# fpc.net
KiCad netlist of a schematic drawn in Altium Designer
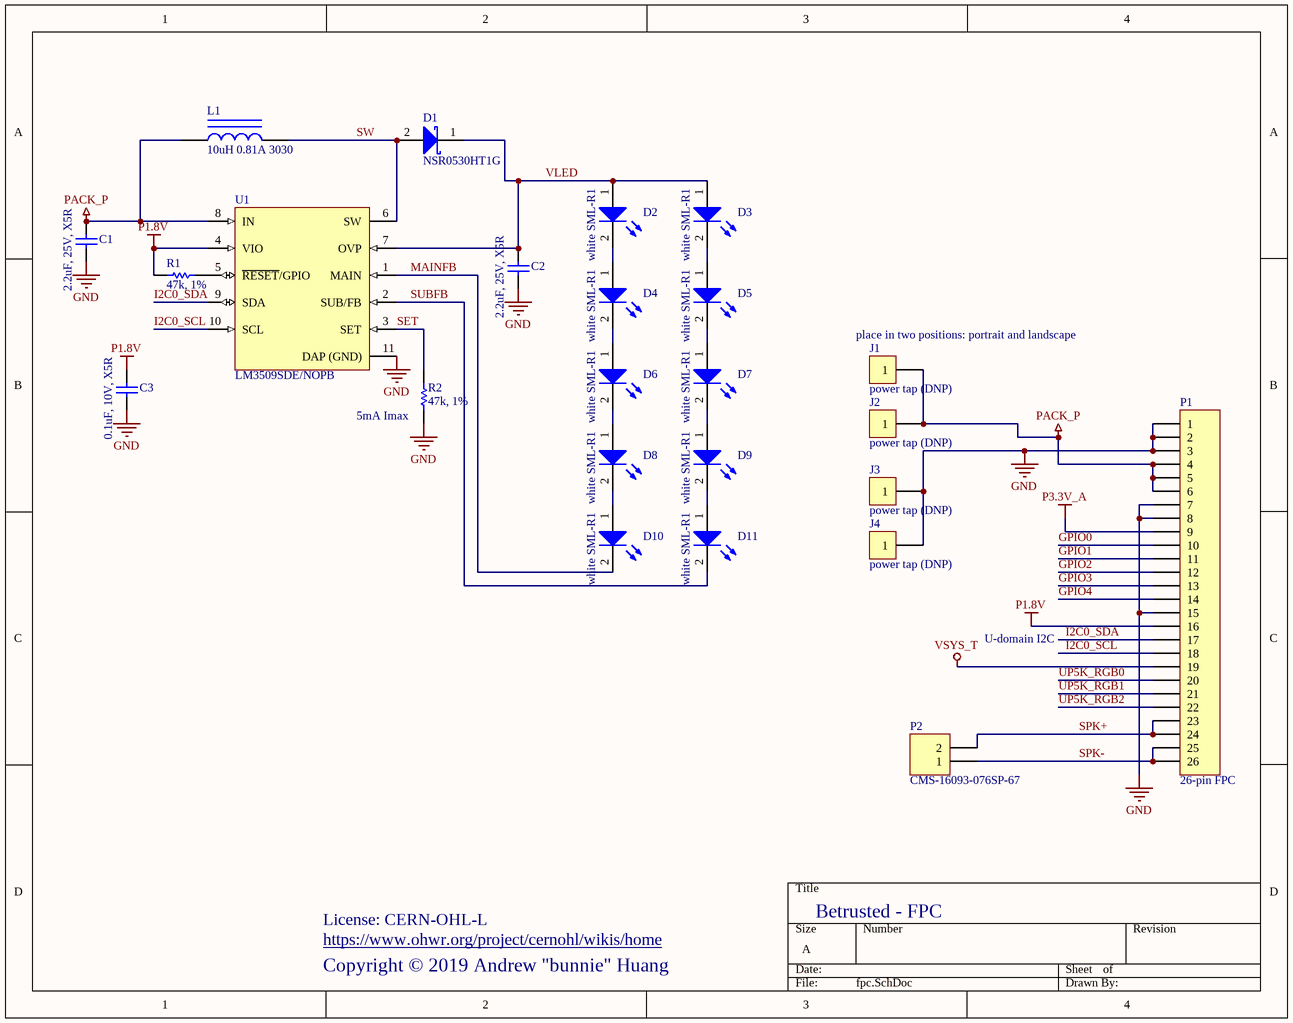
[diagram p0: fpc.SchDoc]

(export (version "E")
  (design (tool "Eeschema 10.0.6"))
  (components
    (comp (ref "C1")
      (value "2.2uF, 25V, X5R")
      (footprint "B_CAP0603")
      (description "Capacitor (Semiconductor SIM Model)")
      (fields (field (name "MPN") "GRM188R61E225MA12D"))
      (libsource (lib "Miscellaneous Devices") (part "Cap Semi"))
    )
    (comp (ref "C2")
      (value "2.2uF, 25V, X5R")
      (footprint "B_CAP0603")
      (description "Capacitor (Semiconductor SIM Model)")
      (fields (field (name "MPN") "GRM188R61E225MA12D"))
      (libsource (lib "Miscellaneous Devices") (part "Cap Semi"))
    )
    (comp (ref "C3")
      (value "0.1uF, 10V, X5R")
      (footprint "B_CAP0402")
      (description "Capacitor (Semiconductor SIM Model)")
      (fields (field (name "MPN") "CL05A104KP5NNNC"))
      (libsource (lib "Miscellaneous Devices") (part "Cap Semi"))
    )
    (comp (ref "D1")
      (value "NSR0530HT1G")
      (footprint "SOD-323")
      (description "Schottky Rectifier")
      (libsource (lib "Miscellaneous Devices") (part "Diode 11DQ03"))
    )
    (comp (ref "D2")
      (value "white SML-R1")
      (footprint "ROHM_SML-R1")
      (description "Red LED")
      (fields (field (name "MPN") "SMLR13WBDW") (field (name "PUBLISHER") "Altium Limited"))
      (libsource (lib "Miscellaneous Devices") (part "LED2"))
    )
    (comp (ref "D3")
      (value "white SML-R1")
      (footprint "ROHM_SML-R1")
      (description "Red LED")
      (fields (field (name "MPN") "SMLR13WBDW") (field (name "PUBLISHER") "Altium Limited"))
      (libsource (lib "Miscellaneous Devices") (part "LED2"))
    )
    (comp (ref "D4")
      (value "white SML-R1")
      (footprint "ROHM_SML-R1")
      (description "Red LED")
      (fields (field (name "MPN") "SMLR13WBDW") (field (name "PUBLISHER") "Altium Limited"))
      (libsource (lib "Miscellaneous Devices") (part "LED2"))
    )
    (comp (ref "D5")
      (value "white SML-R1")
      (footprint "ROHM_SML-R1")
      (description "Red LED")
      (fields (field (name "MPN") "SMLR13WBDW") (field (name "PUBLISHER") "Altium Limited"))
      (libsource (lib "Miscellaneous Devices") (part "LED2"))
    )
    (comp (ref "D6")
      (value "white SML-R1")
      (footprint "ROHM_SML-R1")
      (description "Red LED")
      (fields (field (name "MPN") "SMLR13WBDW") (field (name "PUBLISHER") "Altium Limited"))
      (libsource (lib "Miscellaneous Devices") (part "LED2"))
    )
    (comp (ref "D7")
      (value "white SML-R1")
      (footprint "ROHM_SML-R1")
      (description "Red LED")
      (fields (field (name "MPN") "SMLR13WBDW") (field (name "PUBLISHER") "Altium Limited"))
      (libsource (lib "Miscellaneous Devices") (part "LED2"))
    )
    (comp (ref "D8")
      (value "white SML-R1")
      (footprint "ROHM_SML-R1")
      (description "Red LED")
      (fields (field (name "MPN") "SMLR13WBDW") (field (name "PUBLISHER") "Altium Limited"))
      (libsource (lib "Miscellaneous Devices") (part "LED2"))
    )
    (comp (ref "D9")
      (value "white SML-R1")
      (footprint "ROHM_SML-R1")
      (description "Red LED")
      (fields (field (name "MPN") "SMLR13WBDW") (field (name "PUBLISHER") "Altium Limited"))
      (libsource (lib "Miscellaneous Devices") (part "LED2"))
    )
    (comp (ref "D10")
      (value "white SML-R1")
      (footprint "ROHM_SML-R1")
      (description "Red LED")
      (fields (field (name "MPN") "SMLR13WBDW") (field (name "PUBLISHER") "Altium Limited"))
      (libsource (lib "Miscellaneous Devices") (part "LED2"))
    )
    (comp (ref "D11")
      (value "white SML-R1")
      (footprint "ROHM_SML-R1")
      (description "Red LED")
      (fields (field (name "MPN") "SMLR13WBDW") (field (name "PUBLISHER") "Altium Limited"))
      (libsource (lib "Miscellaneous Devices") (part "LED2"))
    )
    (comp (ref "J1")
      (value "power tap (DNP)")
      (footprint "RESTAP-0603")
      (description "Connector")
      (fields (field (name "MPN") "DNP"))
      (libsource (lib "*") (part "CON1"))
    )
    (comp (ref "J2")
      (value "power tap (DNP)")
      (footprint "RESTAP-0603")
      (description "Connector")
      (fields (field (name "MPN") "DNP"))
      (libsource (lib "*") (part "CON1"))
    )
    (comp (ref "J3")
      (value "power tap (DNP)")
      (footprint "RESTAP-0603")
      (description "Connector")
      (fields (field (name "MPN") "DNP"))
      (libsource (lib "*") (part "CON1"))
    )
    (comp (ref "J4")
      (value "power tap (DNP)")
      (footprint "RESTAP-0603")
      (description "Connector")
      (fields (field (name "MPN") "DNP"))
      (libsource (lib "*") (part "CON1"))
    )
    (comp (ref "L1")
      (value "10uH 0.81A 3030")
      (footprint "B_IND3030_MUR")
      (description "Magnetic-Core Inductor")
      (fields (field (name "MPN") "LQH3NPN100MJRL"))
      (libsource (lib "Miscellaneous Devices") (part "Inductor Iron"))
    )
    (comp (ref "P1")
      (value "26-pin FPC")
      (footprint "HRS_FH34SRJ-26S-FPC")
      (description "26 Pin FPC footprint")
      (fields (field (name "MPN") "DNP"))
      (libsource (lib "commonsch-new") (part "FPC-26"))
    )
    (comp (ref "P2")
      (value "CMS-16093-076SP-67")
      (footprint "CUI_CMS-16093-076SP-67")
      (fields (field (name "PUBLISHER") "Altium Limited"))
      (libsource (lib "Miscellaneous Connectors") (part "Header 2"))
    )
    (comp (ref "R1")
      (value "47k, 1%")
      (footprint "B_RES0402")
      (description "Resistor")
      (fields (field (name "MPN") "ANY"))
      (libsource (lib "Miscellaneous Devices") (part "Res1"))
    )
    (comp (ref "R2")
      (value "47k, 1%")
      (footprint "B_RES0402")
      (description "Resistor")
      (fields (field (name "MPN") "ANY"))
      (libsource (lib "Miscellaneous Devices") (part "Res1"))
    )
    (comp (ref "U1")
      (value "LM3509SDE/NOPB")
      (footprint "DSC0010A_V")
      (libsource (lib "commonsch-new") (part "LM3509SDE/NOPB"))
    )
  )
  (nets
    (net (code "1") (name "/GPIO0") (class "Default")
      (node (ref "P1") (pin "10") (pinfunction "10_10") (pintype "passive"))
    )
    (net (code "2") (name "/GPIO1") (class "Default")
      (node (ref "P1") (pin "11") (pinfunction "11_11") (pintype "passive"))
    )
    (net (code "3") (name "/GPIO2") (class "Default")
      (node (ref "P1") (pin "12") (pinfunction "12_12") (pintype "passive"))
    )
    (net (code "4") (name "/GPIO3") (class "Default")
      (node (ref "P1") (pin "13") (pinfunction "13_13") (pintype "passive"))
    )
    (net (code "5") (name "/GPIO4") (class "Default")
      (node (ref "P1") (pin "14") (pinfunction "14_14") (pintype "passive"))
    )
    (net (code "6") (name "/I2C0_SCL") (class "Default")
      (node (ref "P1") (pin "18") (pinfunction "18_18") (pintype "passive"))
      (node (ref "U1") (pin "10") (pinfunction "SCL_10") (pintype "input"))
    )
    (net (code "7") (name "/I2C0_SDA") (class "Default")
      (node (ref "P1") (pin "17") (pinfunction "17_17") (pintype "passive"))
      (node (ref "U1") (pin "9") (pinfunction "SDA_9") (pintype "bidirectional"))
    )
    (net (code "8") (name "/MAINFB") (class "Default")
      (node (ref "D10") (pin "2") (pinfunction "K_2") (pintype "passive"))
      (node (ref "U1") (pin "1") (pinfunction "MAIN_1") (pintype "input"))
    )
    (net (code "9") (name "/SET") (class "Default")
      (node (ref "R2") (pin "1") (pinfunction "1_1") (pintype "passive"))
      (node (ref "U1") (pin "3") (pinfunction "SET_3") (pintype "input"))
    )
    (net (code "10") (name "/SPK+") (class "Default")
      (node (ref "P1") (pin "23") (pinfunction "23_23") (pintype "passive"))
      (node (ref "P1") (pin "24") (pinfunction "24_24") (pintype "passive"))
      (node (ref "P2") (pin "2") (pinfunction "2_2") (pintype "passive"))
    )
    (net (code "11") (name "/SPK-") (class "Default")
      (node (ref "P1") (pin "25") (pinfunction "25_25") (pintype "passive"))
      (node (ref "P1") (pin "26") (pinfunction "26_26") (pintype "passive"))
      (node (ref "P2") (pin "1") (pinfunction "1_1") (pintype "passive"))
    )
    (net (code "12") (name "/SUBFB") (class "Default")
      (node (ref "D11") (pin "2") (pinfunction "K_2") (pintype "passive"))
      (node (ref "U1") (pin "2") (pinfunction "SUB/FB_2") (pintype "input"))
    )
    (net (code "13") (name "/SW") (class "Default")
      (node (ref "D1") (pin "2") (pinfunction "A_2") (pintype "passive"))
      (node (ref "L1") (pin "2") (pinfunction "2_2") (pintype "passive"))
      (node (ref "U1") (pin "6") (pinfunction "SW_6") (pintype "power_in"))
    )
    (net (code "14") (name "/UP5K_RGB0") (class "Default")
      (node (ref "P1") (pin "20") (pinfunction "20_20") (pintype "passive"))
    )
    (net (code "15") (name "/UP5K_RGB1") (class "Default")
      (node (ref "P1") (pin "21") (pinfunction "21_21") (pintype "passive"))
    )
    (net (code "16") (name "/UP5K_RGB2") (class "Default")
      (node (ref "P1") (pin "22") (pinfunction "22_22") (pintype "passive"))
    )
    (net (code "17") (name "/VLED") (class "Default")
      (node (ref "C2") (pin "1") (pinfunction "1_1") (pintype "passive"))
      (node (ref "D1") (pin "1") (pinfunction "K_1") (pintype "passive"))
      (node (ref "D2") (pin "1") (pinfunction "A_1") (pintype "passive"))
      (node (ref "D3") (pin "1") (pinfunction "A_1") (pintype "passive"))
      (node (ref "U1") (pin "7") (pinfunction "OVP_7") (pintype "input"))
    )
    (net (code "18") (name "GND") (class "Default")
      (node (ref "C1") (pin "2") (pinfunction "2_2") (pintype "passive"))
      (node (ref "C2") (pin "2") (pinfunction "2_2") (pintype "passive"))
      (node (ref "C3") (pin "2") (pinfunction "2_2") (pintype "passive"))
      (node (ref "J3") (pin "1") (pinfunction "1_1") (pintype "passive"))
      (node (ref "J4") (pin "1") (pinfunction "1_1") (pintype "passive"))
      (node (ref "P1") (pin "1") (pinfunction "1_1") (pintype "passive"))
      (node (ref "P1") (pin "15") (pinfunction "15_15") (pintype "passive"))
      (node (ref "P1") (pin "2") (pinfunction "2_2") (pintype "passive"))
      (node (ref "P1") (pin "3") (pinfunction "3_3") (pintype "passive"))
      (node (ref "P1") (pin "7") (pinfunction "7_7") (pintype "passive"))
      (node (ref "P1") (pin "8") (pinfunction "8_8") (pintype "passive"))
      (node (ref "R2") (pin "2") (pinfunction "2_2") (pintype "passive"))
      (node (ref "U1") (pin "11") (pinfunction "DAP_(GND)_11") (pintype "power_in"))
    )
    (net (code "19") (name "Net-(D2-K)") (class "Default")
      (node (ref "D2") (pin "2") (pinfunction "K_2") (pintype "passive"))
      (node (ref "D4") (pin "1") (pinfunction "A_1") (pintype "passive"))
    )
    (net (code "20") (name "Net-(D3-K)") (class "Default")
      (node (ref "D3") (pin "2") (pinfunction "K_2") (pintype "passive"))
      (node (ref "D5") (pin "1") (pinfunction "A_1") (pintype "passive"))
    )
    (net (code "21") (name "Net-(D4-K)") (class "Default")
      (node (ref "D4") (pin "2") (pinfunction "K_2") (pintype "passive"))
      (node (ref "D6") (pin "1") (pinfunction "A_1") (pintype "passive"))
    )
    (net (code "22") (name "Net-(D5-K)") (class "Default")
      (node (ref "D5") (pin "2") (pinfunction "K_2") (pintype "passive"))
      (node (ref "D7") (pin "1") (pinfunction "A_1") (pintype "passive"))
    )
    (net (code "23") (name "Net-(D6-K)") (class "Default")
      (node (ref "D6") (pin "2") (pinfunction "K_2") (pintype "passive"))
      (node (ref "D8") (pin "1") (pinfunction "A_1") (pintype "passive"))
    )
    (net (code "24") (name "Net-(D7-K)") (class "Default")
      (node (ref "D7") (pin "2") (pinfunction "K_2") (pintype "passive"))
      (node (ref "D9") (pin "1") (pinfunction "A_1") (pintype "passive"))
    )
    (net (code "25") (name "Net-(D10-A)") (class "Default")
      (node (ref "D10") (pin "1") (pinfunction "A_1") (pintype "passive"))
      (node (ref "D8") (pin "2") (pinfunction "K_2") (pintype "passive"))
    )
    (net (code "26") (name "Net-(D11-A)") (class "Default")
      (node (ref "D11") (pin "1") (pinfunction "A_1") (pintype "passive"))
      (node (ref "D9") (pin "2") (pinfunction "K_2") (pintype "passive"))
    )
    (net (code "27") (name "Net-(U1-~{RESET}{slash}GPIO)") (class "Default")
      (node (ref "R1") (pin "2") (pinfunction "2_2") (pintype "passive"))
      (node (ref "U1") (pin "5") (pinfunction "~{RESET}/GPIO_5") (pintype "bidirectional"))
    )
    (net (code "28") (name "P1.8V") (class "Default")
      (node (ref "C3") (pin "1") (pinfunction "1_1") (pintype "passive"))
      (node (ref "P1") (pin "16") (pinfunction "16_16") (pintype "passive"))
      (node (ref "R1") (pin "1") (pinfunction "1_1") (pintype "passive"))
      (node (ref "U1") (pin "4") (pinfunction "VIO_4") (pintype "input"))
    )
    (net (code "29") (name "P3.3V_A") (class "Default")
      (node (ref "P1") (pin "9") (pinfunction "9_9") (pintype "passive"))
    )
    (net (code "30") (name "PACK_P") (class "Default")
      (node (ref "C1") (pin "1") (pinfunction "1_1") (pintype "passive"))
      (node (ref "J1") (pin "1") (pinfunction "1_1") (pintype "passive"))
      (node (ref "J2") (pin "1") (pinfunction "1_1") (pintype "passive"))
      (node (ref "L1") (pin "1") (pinfunction "1_1") (pintype "passive"))
      (node (ref "P1") (pin "4") (pinfunction "4_4") (pintype "passive"))
      (node (ref "P1") (pin "5") (pinfunction "5_5") (pintype "passive"))
      (node (ref "P1") (pin "6") (pinfunction "6_6") (pintype "passive"))
      (node (ref "U1") (pin "8") (pinfunction "IN_8") (pintype "input"))
    )
    (net (code "31") (name "VSYS_T") (class "Default")
      (node (ref "P1") (pin "19") (pinfunction "19_19") (pintype "passive"))
    )
  )
)
